# ToF_Circuit.net
KiCad netlist of a schematic drawn in EAGLE
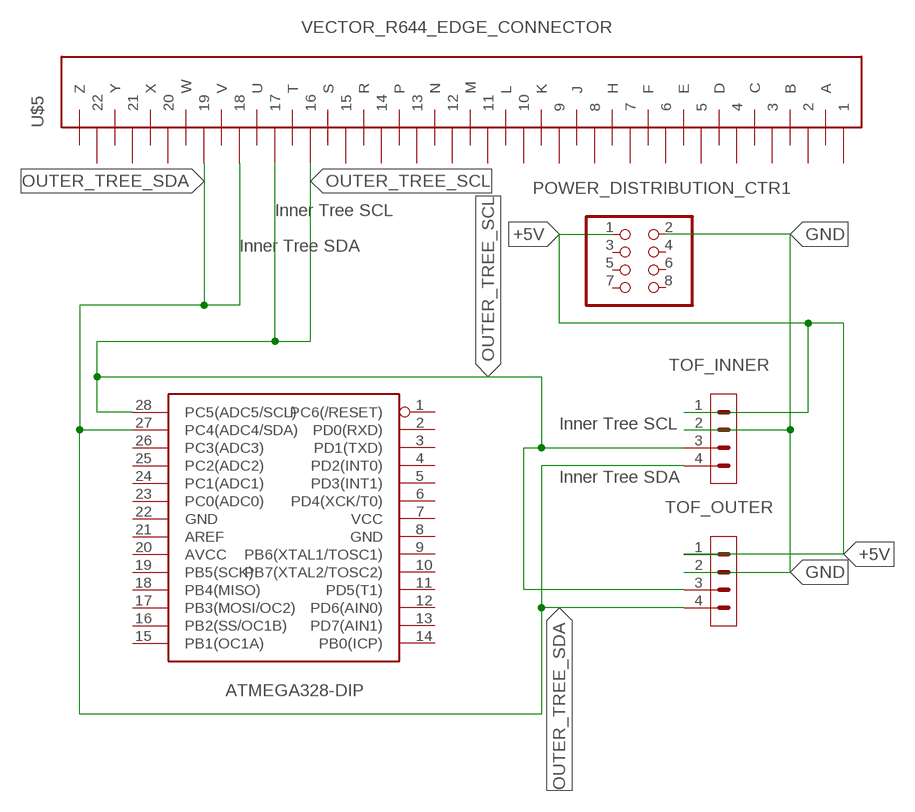
[diagram p0: schematic, sheet 1]

(export (version "E")
  (design (tool "Eeschema 10.0.6"))
  (components
    (comp (ref "POWER_DISTRIBUTION_CTR1")
      (value "PINHD-2X4")
      (footprint "eagle-import:2X04")
      (libsource (lib "eagle-import") (part "PINHD-2X4"))
    )
    (comp (ref "TOF_INNER")
      (value "PINHD-1X4")
      (footprint "eagle-import:1X04")
      (libsource (lib "eagle-import") (part "PINHD-1X4"))
    )
    (comp (ref "TOF_OUTER")
      (value "PINHD-1X4")
      (footprint "eagle-import:1X04")
      (libsource (lib "eagle-import") (part "PINHD-1X4"))
    )
    (comp (ref "U$5")
      (value "VECTOR_R644_EDGE_CONNECTOR")
      (footprint "eagle-import:VECTOR44")
      (libsource (lib "eagle-import") (part "VECTOR_R644_EDGE_CONNECTOR"))
    )
    (comp (ref "U$10")
      (value "ATMEGA328-DIP")
      (footprint "eagle-import:DIP28")
      (libsource (lib "eagle-import") (part "ATMEGA328-DIP"))
    )
  )
  (nets
    (net (code "1") (name "+5V") (class "Default")
      (node (ref "POWER_DISTRIBUTION_CTR1") (pin "1") (pinfunction "1_1") (pintype "passive"))
      (node (ref "TOF_INNER") (pin "1") (pinfunction "1_1") (pintype "passive"))
      (node (ref "TOF_OUTER") (pin "1") (pinfunction "1_1") (pintype "passive"))
    )
    (net (code "2") (name "GND") (class "Default")
      (node (ref "POWER_DISTRIBUTION_CTR1") (pin "2") (pinfunction "2_2") (pintype "passive"))
      (node (ref "TOF_INNER") (pin "2") (pinfunction "2_2") (pintype "passive"))
      (node (ref "TOF_OUTER") (pin "2") (pinfunction "2_2") (pintype "passive"))
    )
    (net (code "3") (name "OUTER_TREE_SCL") (class "Default")
      (node (ref "TOF_INNER") (pin "3") (pinfunction "3_3") (pintype "passive"))
      (node (ref "TOF_OUTER") (pin "3") (pinfunction "3_3") (pintype "passive"))
      (node (ref "U$10") (pin "28") (pinfunction "PC5(ADC5/SCL)_28") (pintype "bidirectional"))
      (node (ref "U$5") (pin "P$16") (pinfunction "16_P$16") (pintype "bidirectional"))
      (node (ref "U$5") (pin "P$17") (pinfunction "17_P$17") (pintype "bidirectional"))
    )
    (net (code "4") (name "OUTER_TREE_SDA") (class "Default")
      (node (ref "TOF_INNER") (pin "4") (pinfunction "4_4") (pintype "passive"))
      (node (ref "TOF_OUTER") (pin "4") (pinfunction "4_4") (pintype "passive"))
      (node (ref "U$10") (pin "27") (pinfunction "PC4(ADC4/SDA)_27") (pintype "bidirectional"))
      (node (ref "U$5") (pin "P$18") (pinfunction "18_P$18") (pintype "bidirectional"))
      (node (ref "U$5") (pin "P$19") (pinfunction "19_P$19") (pintype "bidirectional"))
    )
    (net (code "5") (name "unconnected-(POWER_DISTRIBUTION_CTR1-Pad3)") (class "Default")
      (node (ref "POWER_DISTRIBUTION_CTR1") (pin "3") (pinfunction "3_3") (pintype "passive"))
    )
    (net (code "6") (name "unconnected-(POWER_DISTRIBUTION_CTR1-Pad4)") (class "Default")
      (node (ref "POWER_DISTRIBUTION_CTR1") (pin "4") (pinfunction "4_4") (pintype "passive"))
    )
    (net (code "7") (name "unconnected-(POWER_DISTRIBUTION_CTR1-Pad5)") (class "Default")
      (node (ref "POWER_DISTRIBUTION_CTR1") (pin "5") (pinfunction "5_5") (pintype "passive"))
    )
    (net (code "8") (name "unconnected-(POWER_DISTRIBUTION_CTR1-Pad6)") (class "Default")
      (node (ref "POWER_DISTRIBUTION_CTR1") (pin "6") (pinfunction "6_6") (pintype "passive"))
    )
    (net (code "9") (name "unconnected-(POWER_DISTRIBUTION_CTR1-Pad7)") (class "Default")
      (node (ref "POWER_DISTRIBUTION_CTR1") (pin "7") (pinfunction "7_7") (pintype "passive"))
    )
    (net (code "10") (name "unconnected-(POWER_DISTRIBUTION_CTR1-Pad8)") (class "Default")
      (node (ref "POWER_DISTRIBUTION_CTR1") (pin "8") (pinfunction "8_8") (pintype "passive"))
    )
    (net (code "11") (name "unconnected-(U$5-1-PadP$1)") (class "Default")
      (node (ref "U$5") (pin "P$1") (pinfunction "1_P$1") (pintype "bidirectional"))
    )
    (net (code "12") (name "unconnected-(U$5-2-PadP$2)") (class "Default")
      (node (ref "U$5") (pin "P$2") (pinfunction "2_P$2") (pintype "bidirectional"))
    )
    (net (code "13") (name "unconnected-(U$5-3-PadP$3)") (class "Default")
      (node (ref "U$5") (pin "P$3") (pinfunction "3_P$3") (pintype "bidirectional"))
    )
    (net (code "14") (name "unconnected-(U$5-4-PadP$4)") (class "Default")
      (node (ref "U$5") (pin "P$4") (pinfunction "4_P$4") (pintype "bidirectional"))
    )
    (net (code "15") (name "unconnected-(U$5-5-PadP$5)") (class "Default")
      (node (ref "U$5") (pin "P$5") (pinfunction "5_P$5") (pintype "bidirectional"))
    )
    (net (code "16") (name "unconnected-(U$5-6-PadP$6)") (class "Default")
      (node (ref "U$5") (pin "P$6") (pinfunction "6_P$6") (pintype "bidirectional"))
    )
    (net (code "17") (name "unconnected-(U$5-7-PadP$7)") (class "Default")
      (node (ref "U$5") (pin "P$7") (pinfunction "7_P$7") (pintype "bidirectional"))
    )
    (net (code "18") (name "unconnected-(U$5-8-PadP$8)") (class "Default")
      (node (ref "U$5") (pin "P$8") (pinfunction "8_P$8") (pintype "bidirectional"))
    )
    (net (code "19") (name "unconnected-(U$5-9-PadP$9)") (class "Default")
      (node (ref "U$5") (pin "P$9") (pinfunction "9_P$9") (pintype "bidirectional"))
    )
    (net (code "20") (name "unconnected-(U$5-10-PadP$10)") (class "Default")
      (node (ref "U$5") (pin "P$10") (pinfunction "10_P$10") (pintype "bidirectional"))
    )
    (net (code "21") (name "unconnected-(U$5-11-PadP$11)") (class "Default")
      (node (ref "U$5") (pin "P$11") (pinfunction "11_P$11") (pintype "bidirectional"))
    )
    (net (code "22") (name "unconnected-(U$5-12-PadP$12)") (class "Default")
      (node (ref "U$5") (pin "P$12") (pinfunction "12_P$12") (pintype "bidirectional"))
    )
    (net (code "23") (name "unconnected-(U$5-13-PadP$13)") (class "Default")
      (node (ref "U$5") (pin "P$13") (pinfunction "13_P$13") (pintype "bidirectional"))
    )
    (net (code "24") (name "unconnected-(U$5-14-PadP$14)") (class "Default")
      (node (ref "U$5") (pin "P$14") (pinfunction "14_P$14") (pintype "bidirectional"))
    )
    (net (code "25") (name "unconnected-(U$5-15-PadP$15)") (class "Default")
      (node (ref "U$5") (pin "P$15") (pinfunction "15_P$15") (pintype "bidirectional"))
    )
    (net (code "26") (name "unconnected-(U$5-20-PadP$20)") (class "Default")
      (node (ref "U$5") (pin "P$20") (pinfunction "20_P$20") (pintype "bidirectional"))
    )
    (net (code "27") (name "unconnected-(U$5-21-PadP$21)") (class "Default")
      (node (ref "U$5") (pin "P$21") (pinfunction "21_P$21") (pintype "bidirectional"))
    )
    (net (code "28") (name "unconnected-(U$5-22-PadP$22)") (class "Default")
      (node (ref "U$5") (pin "P$22") (pinfunction "22_P$22") (pintype "bidirectional"))
    )
    (net (code "29") (name "unconnected-(U$5-A-PadP$A)") (class "Default")
      (node (ref "U$5") (pin "P$A") (pinfunction "A_P$A") (pintype "bidirectional"))
    )
    (net (code "30") (name "unconnected-(U$5-B-PadP$B)") (class "Default")
      (node (ref "U$5") (pin "P$B") (pinfunction "B_P$B") (pintype "bidirectional"))
    )
    (net (code "31") (name "unconnected-(U$5-C-PadP$C)") (class "Default")
      (node (ref "U$5") (pin "P$C") (pinfunction "C_P$C") (pintype "bidirectional"))
    )
    (net (code "32") (name "unconnected-(U$5-D-PadP$D)") (class "Default")
      (node (ref "U$5") (pin "P$D") (pinfunction "D_P$D") (pintype "bidirectional"))
    )
    (net (code "33") (name "unconnected-(U$5-E-PadP$E)") (class "Default")
      (node (ref "U$5") (pin "P$E") (pinfunction "E_P$E") (pintype "bidirectional"))
    )
    (net (code "34") (name "unconnected-(U$5-F-PadP$F)") (class "Default")
      (node (ref "U$5") (pin "P$F") (pinfunction "F_P$F") (pintype "bidirectional"))
    )
    (net (code "35") (name "unconnected-(U$5-H-PadP$H)") (class "Default")
      (node (ref "U$5") (pin "P$H") (pinfunction "H_P$H") (pintype "bidirectional"))
    )
    (net (code "36") (name "unconnected-(U$5-J-PadP$J)") (class "Default")
      (node (ref "U$5") (pin "P$J") (pinfunction "J_P$J") (pintype "bidirectional"))
    )
    (net (code "37") (name "unconnected-(U$5-K-PadP$K)") (class "Default")
      (node (ref "U$5") (pin "P$K") (pinfunction "K_P$K") (pintype "bidirectional"))
    )
    (net (code "38") (name "unconnected-(U$5-L-PadP$L)") (class "Default")
      (node (ref "U$5") (pin "P$L") (pinfunction "L_P$L") (pintype "bidirectional"))
    )
    (net (code "39") (name "unconnected-(U$5-M-PadP$M)") (class "Default")
      (node (ref "U$5") (pin "P$M") (pinfunction "M_P$M") (pintype "bidirectional"))
    )
    (net (code "40") (name "unconnected-(U$5-N-PadP$N)") (class "Default")
      (node (ref "U$5") (pin "P$N") (pinfunction "N_P$N") (pintype "bidirectional"))
    )
    (net (code "41") (name "unconnected-(U$5-P-PadP$P)") (class "Default")
      (node (ref "U$5") (pin "P$P") (pinfunction "P_P$P") (pintype "bidirectional"))
    )
    (net (code "42") (name "unconnected-(U$5-R-PadP$R)") (class "Default")
      (node (ref "U$5") (pin "P$R") (pinfunction "R_P$R") (pintype "bidirectional"))
    )
    (net (code "43") (name "unconnected-(U$5-S-PadP$S)") (class "Default")
      (node (ref "U$5") (pin "P$S") (pinfunction "S_P$S") (pintype "bidirectional"))
    )
    (net (code "44") (name "unconnected-(U$5-T-PadP$T)") (class "Default")
      (node (ref "U$5") (pin "P$T") (pinfunction "T_P$T") (pintype "bidirectional"))
    )
    (net (code "45") (name "unconnected-(U$5-U-PadP$U)") (class "Default")
      (node (ref "U$5") (pin "P$U") (pinfunction "U_P$U") (pintype "bidirectional"))
    )
    (net (code "46") (name "unconnected-(U$5-V-PadP$V)") (class "Default")
      (node (ref "U$5") (pin "P$V") (pinfunction "V_P$V") (pintype "bidirectional"))
    )
    (net (code "47") (name "unconnected-(U$5-W-PadP$W)") (class "Default")
      (node (ref "U$5") (pin "P$W") (pinfunction "W_P$W") (pintype "bidirectional"))
    )
    (net (code "48") (name "unconnected-(U$5-X-PadP$X)") (class "Default")
      (node (ref "U$5") (pin "P$X") (pinfunction "X_P$X") (pintype "bidirectional"))
    )
    (net (code "49") (name "unconnected-(U$5-Y-PadP$Y)") (class "Default")
      (node (ref "U$5") (pin "P$Y") (pinfunction "Y_P$Y") (pintype "bidirectional"))
    )
    (net (code "50") (name "unconnected-(U$5-Z-PadP$Z)") (class "Default")
      (node (ref "U$5") (pin "P$Z") (pinfunction "Z_P$Z") (pintype "bidirectional"))
    )
    (net (code "51") (name "unconnected-(U$10-AREF-Pad21)") (class "Default")
      (node (ref "U$10") (pin "21") (pinfunction "AREF_21") (pintype "bidirectional"))
    )
    (net (code "52") (name "unconnected-(U$10-AVCC-Pad20)") (class "Default")
      (node (ref "U$10") (pin "20") (pinfunction "AVCC_20") (pintype "bidirectional"))
    )
    (net (code "53") (name "unconnected-(U$10-GND-Pad8)") (class "Default")
      (node (ref "U$10") (pin "8") (pinfunction "GND_8") (pintype "bidirectional"))
    )
    (net (code "54") (name "unconnected-(U$10-GND-Pad22)") (class "Default")
      (node (ref "U$10") (pin "22") (pinfunction "GND_22") (pintype "bidirectional"))
    )
    (net (code "55") (name "unconnected-(U$10-PB0(ICP)-Pad14)") (class "Default")
      (node (ref "U$10") (pin "14") (pinfunction "PB0(ICP)_14") (pintype "bidirectional"))
    )
    (net (code "56") (name "unconnected-(U$10-PB1(OC1A)-Pad15)") (class "Default")
      (node (ref "U$10") (pin "15") (pinfunction "PB1(OC1A)_15") (pintype "bidirectional"))
    )
    (net (code "57") (name "unconnected-(U$10-PB2(SS{slash}OC1B)-Pad16)") (class "Default")
      (node (ref "U$10") (pin "16") (pinfunction "PB2(SS/OC1B)_16") (pintype "bidirectional"))
    )
    (net (code "58") (name "unconnected-(U$10-PB3(MOSI{slash}OC2)-Pad17)") (class "Default")
      (node (ref "U$10") (pin "17") (pinfunction "PB3(MOSI/OC2)_17") (pintype "bidirectional"))
    )
    (net (code "59") (name "unconnected-(U$10-PB4(MISO)-Pad18)") (class "Default")
      (node (ref "U$10") (pin "18") (pinfunction "PB4(MISO)_18") (pintype "bidirectional"))
    )
    (net (code "60") (name "unconnected-(U$10-PB5(SCK)-Pad19)") (class "Default")
      (node (ref "U$10") (pin "19") (pinfunction "PB5(SCK)_19") (pintype "bidirectional"))
    )
    (net (code "61") (name "unconnected-(U$10-PB6(XTAL1{slash}TOSC1)-Pad9)") (class "Default")
      (node (ref "U$10") (pin "9") (pinfunction "PB6(XTAL1/TOSC1)_9") (pintype "bidirectional"))
    )
    (net (code "62") (name "unconnected-(U$10-PB7(XTAL2{slash}TOSC2)-Pad10)") (class "Default")
      (node (ref "U$10") (pin "10") (pinfunction "PB7(XTAL2/TOSC2)_10") (pintype "bidirectional"))
    )
    (net (code "63") (name "unconnected-(U$10-PC0(ADC0)-Pad23)") (class "Default")
      (node (ref "U$10") (pin "23") (pinfunction "PC0(ADC0)_23") (pintype "bidirectional"))
    )
    (net (code "64") (name "unconnected-(U$10-PC1(ADC1)-Pad24)") (class "Default")
      (node (ref "U$10") (pin "24") (pinfunction "PC1(ADC1)_24") (pintype "bidirectional"))
    )
    (net (code "65") (name "unconnected-(U$10-PC2(ADC2)-Pad25)") (class "Default")
      (node (ref "U$10") (pin "25") (pinfunction "PC2(ADC2)_25") (pintype "bidirectional"))
    )
    (net (code "66") (name "unconnected-(U$10-PC3(ADC3)-Pad26)") (class "Default")
      (node (ref "U$10") (pin "26") (pinfunction "PC3(ADC3)_26") (pintype "bidirectional"))
    )
    (net (code "67") (name "unconnected-(U$10-PC6({slash}RESET)-Pad1)") (class "Default")
      (node (ref "U$10") (pin "1") (pinfunction "PC6(/RESET)_1") (pintype "bidirectional"))
    )
    (net (code "68") (name "unconnected-(U$10-PD0(RXD)-Pad2)") (class "Default")
      (node (ref "U$10") (pin "2") (pinfunction "PD0(RXD)_2") (pintype "bidirectional"))
    )
    (net (code "69") (name "unconnected-(U$10-PD1(TXD)-Pad3)") (class "Default")
      (node (ref "U$10") (pin "3") (pinfunction "PD1(TXD)_3") (pintype "bidirectional"))
    )
    (net (code "70") (name "unconnected-(U$10-PD2(INT0)-Pad4)") (class "Default")
      (node (ref "U$10") (pin "4") (pinfunction "PD2(INT0)_4") (pintype "bidirectional"))
    )
    (net (code "71") (name "unconnected-(U$10-PD3(INT1)-Pad5)") (class "Default")
      (node (ref "U$10") (pin "5") (pinfunction "PD3(INT1)_5") (pintype "bidirectional"))
    )
    (net (code "72") (name "unconnected-(U$10-PD4(XCK{slash}T0)-Pad6)") (class "Default")
      (node (ref "U$10") (pin "6") (pinfunction "PD4(XCK/T0)_6") (pintype "bidirectional"))
    )
    (net (code "73") (name "unconnected-(U$10-PD5(T1)-Pad11)") (class "Default")
      (node (ref "U$10") (pin "11") (pinfunction "PD5(T1)_11") (pintype "bidirectional"))
    )
    (net (code "74") (name "unconnected-(U$10-PD6(AIN0)-Pad12)") (class "Default")
      (node (ref "U$10") (pin "12") (pinfunction "PD6(AIN0)_12") (pintype "bidirectional"))
    )
    (net (code "75") (name "unconnected-(U$10-PD7(AIN1)-Pad13)") (class "Default")
      (node (ref "U$10") (pin "13") (pinfunction "PD7(AIN1)_13") (pintype "bidirectional"))
    )
    (net (code "76") (name "unconnected-(U$10-VCC-Pad7)") (class "Default")
      (node (ref "U$10") (pin "7") (pinfunction "VCC_7") (pintype "bidirectional"))
    )
  )
)
